# keyboard_board_schematic.net
KiCad netlist of a schematic drawn in EasyEDA Pro
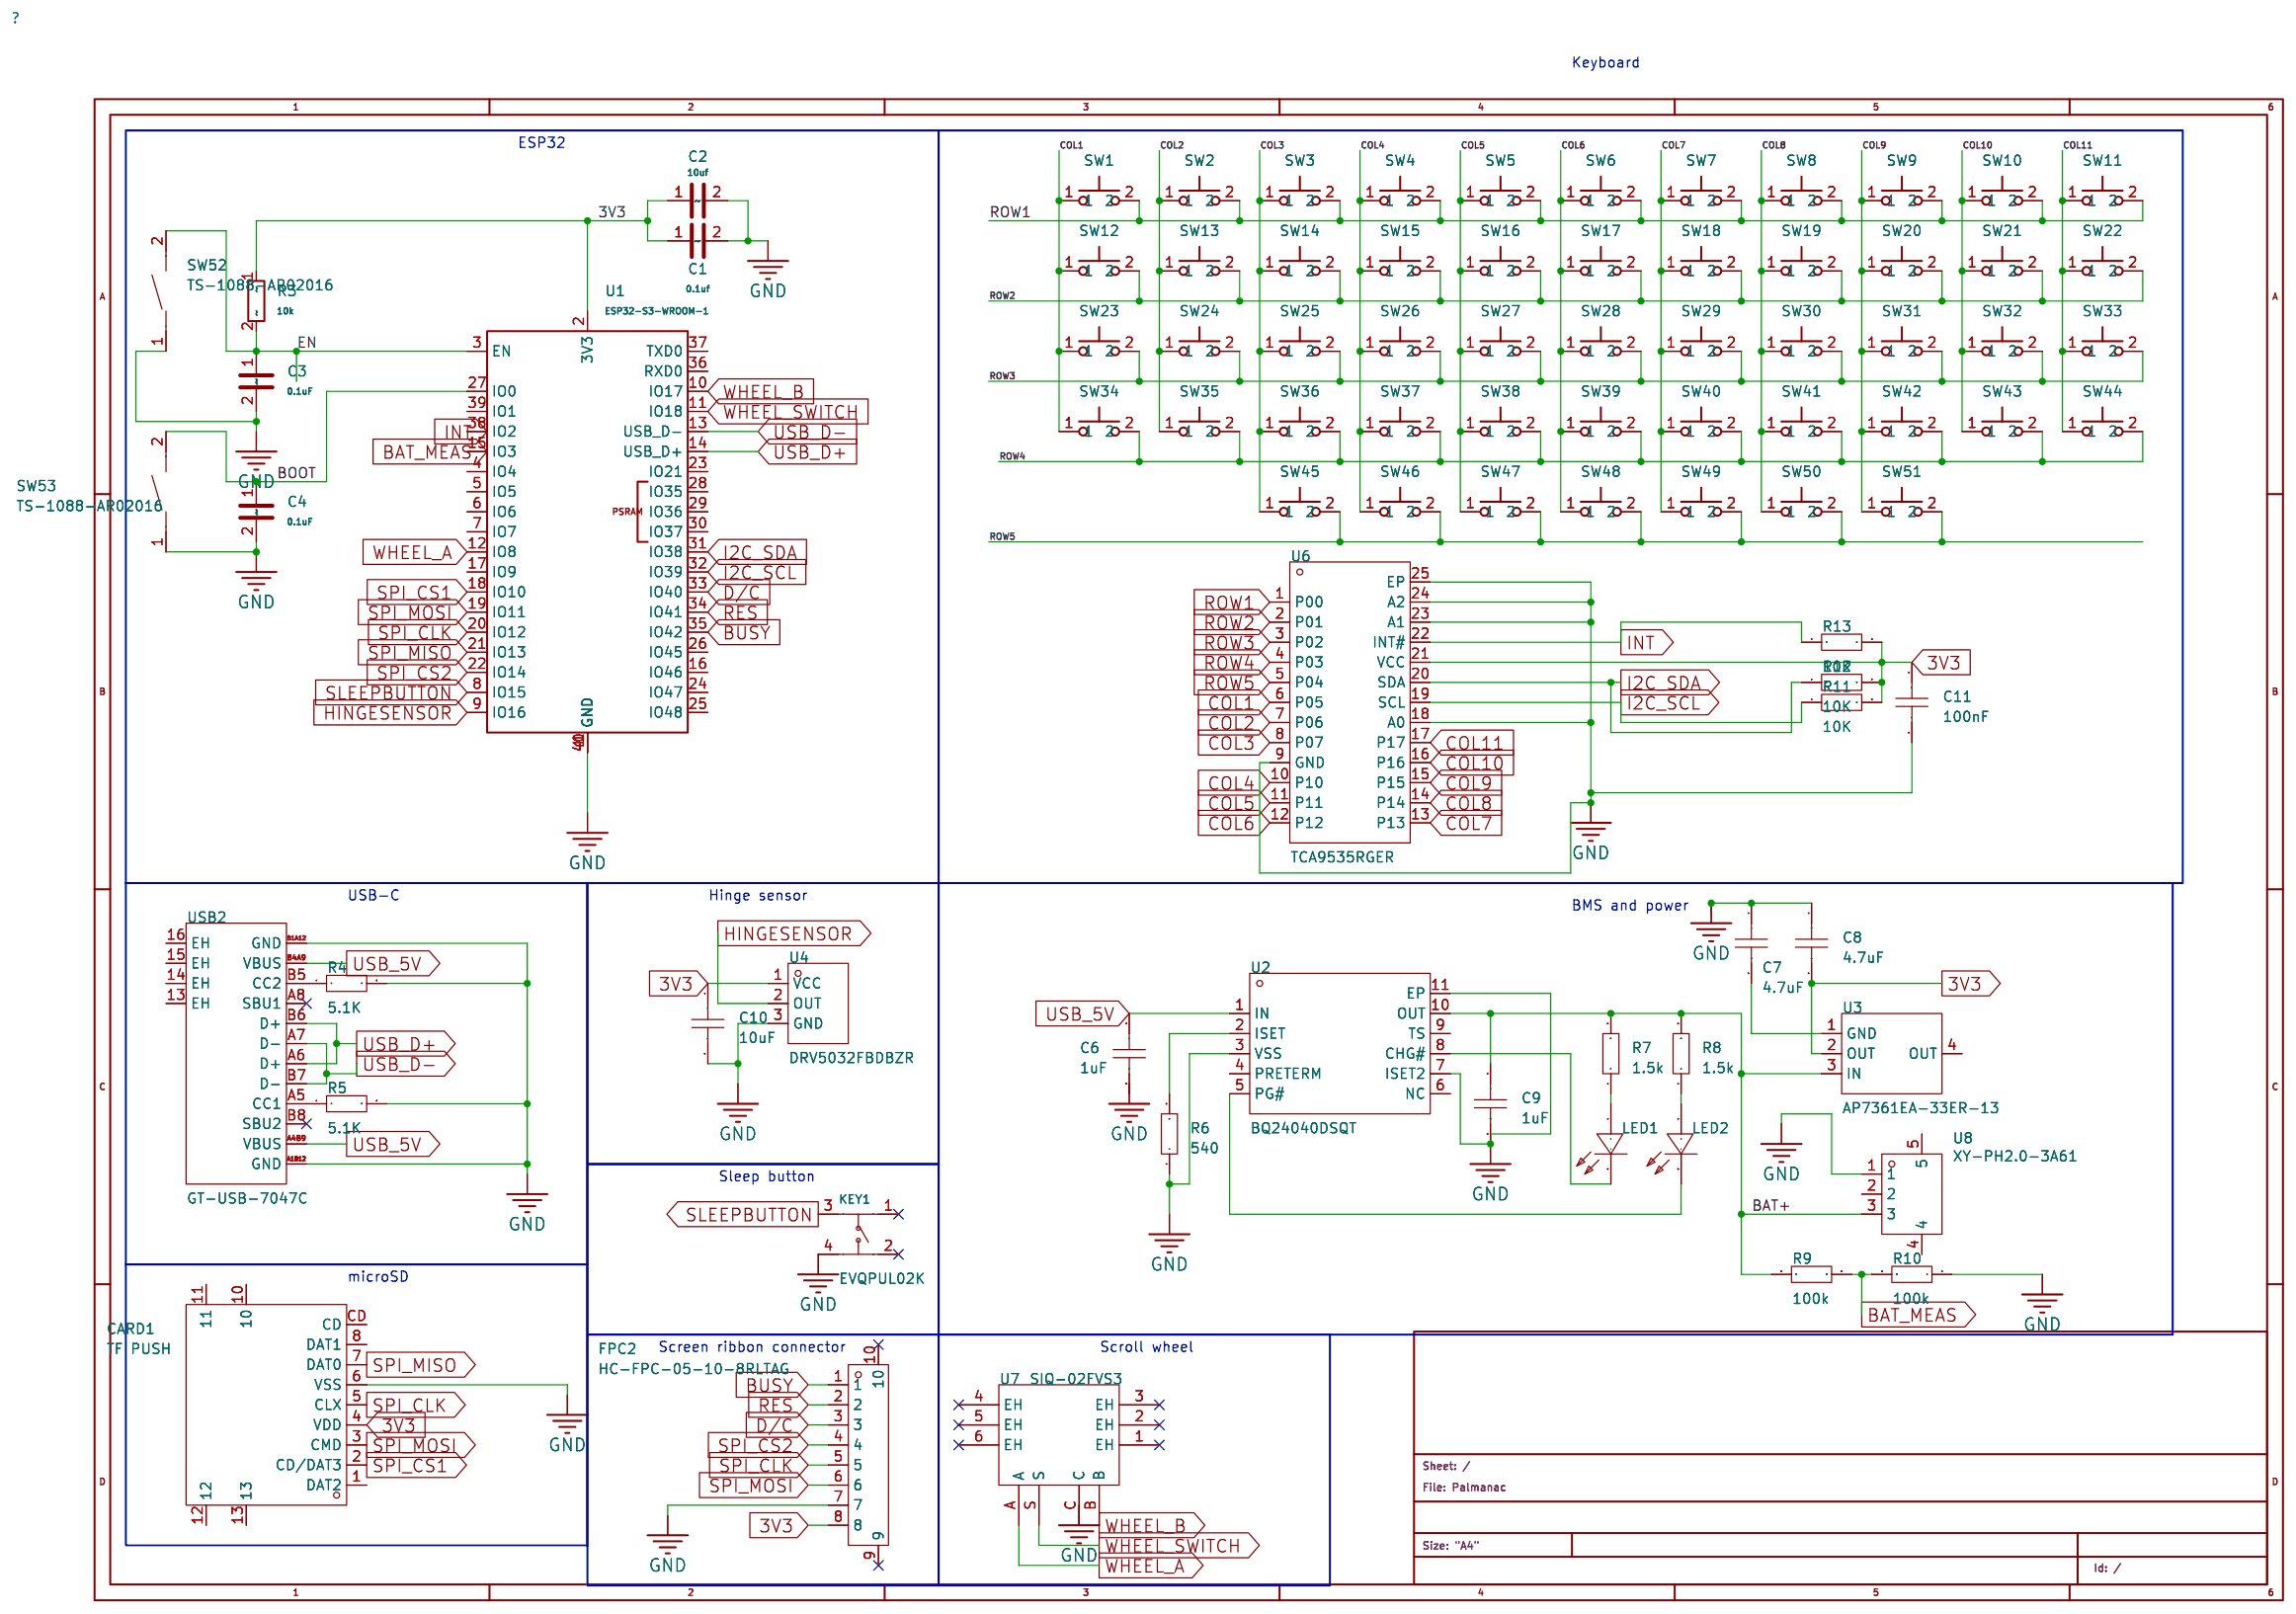
[diagram p0: schematic sheet]

(export (version "E")
  (design (tool "Eeschema 10.0.6"))
  (components
    (comp (ref "C1")
      (value "0.1uf")
      (description "Unpolarized capacitor")
      (libsource (lib "easyedapro") (part "Device_C"))
    )
    (comp (ref "C2")
      (value "10uf")
      (description "Unpolarized capacitor")
      (libsource (lib "easyedapro") (part "Device_C"))
    )
    (comp (ref "C3")
      (value "0.1uF")
      (description "Unpolarized capacitor")
      (libsource (lib "easyedapro") (part "Device_C"))
    )
    (comp (ref "C4")
      (value "0.1uF")
      (description "Unpolarized capacitor")
      (libsource (lib "easyedapro") (part "Device_C"))
    )
    (comp (ref "C6") (value "1uF") (footprint "easyedapro:C0603") (libsource (lib "easyedapro") (part "CAP")))
    (comp (ref "C7")
      (value "4.7uF")
      (footprint "easyedapro:C0603")
      (libsource (lib "easyedapro") (part "CAP"))
    )
    (comp (ref "C8")
      (value "4.7uF")
      (footprint "easyedapro:C0603")
      (libsource (lib "easyedapro") (part "CAP"))
    )
    (comp (ref "C9") (value "1uF") (footprint "easyedapro:C0603") (libsource (lib "easyedapro") (part "CAP")))
    (comp (ref "C10")
      (value "10uF")
      (footprint "easyedapro:C0603")
      (libsource (lib "easyedapro") (part "CAP"))
    )
    (comp (ref "C11")
      (value "100nF")
      (footprint "easyedapro:C0603")
      (libsource (lib "easyedapro") (part "CAP"))
    )
    (comp (ref "CARD1")
      (value "TF PUSH")
      (footprint "easyedapro:TF-SMD_TF-PUSH")
      (fields (field (name "Manufacturer") "SHOU HAN(首韩)"))
      (libsource (lib "easyedapro") (part "TF PUSH"))
    )
    (comp (ref "FPC2")
      (value "HC-FPC-05-10-8RLTAG")
      (footprint "easyedapro:FPC-SMD_8P-P0.50_HCTL_HC-FPC-05-10-8RLTAG")
      (fields (field (name "Manufacturer") "HCTL(华灿天禄)"))
      (libsource (lib "easyedapro") (part "HC-FPC-05-10-8RLTAG"))
    )
    (comp (ref "KEY1")
      (value "EVQPUL02K")
      (footprint "easyedapro:KEY-SMD_4P-L4.7-W3.5-P1.70-LS6.4-EH")
      (fields (field (name "Manufacturer") "PANASONIC(松下)"))
      (libsource (lib "easyedapro") (part "EVQPUL02K"))
    )
    (comp (ref "LED1")
      (value "NCD0805R1")
      (footprint "easyedapro:LED0805-R-RD")
      (fields (field (name "Manufacturer") "国星光电"))
      (libsource (lib "easyedapro") (part "FC-2012HRK-620D"))
    )
    (comp (ref "LED2")
      (value "NCD0805R1")
      (footprint "easyedapro:LED0805-R-RD")
      (fields (field (name "Manufacturer") "国星光电"))
      (libsource (lib "easyedapro") (part "FC-2012HRK-620D"))
    )
    (comp (ref "R3") (value "10k") (description "Resistor") (libsource (lib "easyedapro") (part "Device_R")))
    (comp (ref "R4")
      (value "5.1K")
      (footprint "easyedapro:R0603")
      (libsource (lib "easyedapro") (part "Res"))
    )
    (comp (ref "R5")
      (value "5.1K")
      (footprint "easyedapro:R0603")
      (libsource (lib "easyedapro") (part "Res"))
    )
    (comp (ref "R6") (value "540") (footprint "easyedapro:R0603") (libsource (lib "easyedapro") (part "Res")))
    (comp (ref "R7")
      (value "1.5k")
      (footprint "easyedapro:R0603")
      (libsource (lib "easyedapro") (part "Res"))
    )
    (comp (ref "R8")
      (value "1.5k")
      (footprint "easyedapro:R0603")
      (libsource (lib "easyedapro") (part "Res"))
    )
    (comp (ref "R9")
      (value "100k")
      (footprint "easyedapro:R0603")
      (libsource (lib "easyedapro") (part "Res"))
    )
    (comp (ref "R10")
      (value "100k")
      (footprint "easyedapro:R0603")
      (libsource (lib "easyedapro") (part "Res"))
    )
    (comp (ref "R11")
      (value "10K")
      (footprint "easyedapro:R0603")
      (libsource (lib "easyedapro") (part "Res"))
    )
    (comp (ref "R12")
      (value "10K")
      (footprint "easyedapro:R0603")
      (libsource (lib "easyedapro") (part "Res"))
    )
    (comp (ref "R13")
      (value "10K")
      (footprint "easyedapro:R0603")
      (libsource (lib "easyedapro") (part "Res"))
    )
    (comp (ref "SW1")
      (value "SW_Push")
      (footprint "easyedapro:Switch_Dome_7MM")
      (description "Push button switch, generic, two pins")
      (libsource (lib "easyedapro") (part "Switch_SW_Push"))
    )
    (comp (ref "SW2")
      (value "SW_Push")
      (footprint "easyedapro:Switch_Dome_7MM")
      (description "Push button switch, generic, two pins")
      (libsource (lib "easyedapro") (part "Switch_SW_Push"))
    )
    (comp (ref "SW3")
      (value "SW_Push")
      (footprint "easyedapro:Switch_Dome_7MM")
      (description "Push button switch, generic, two pins")
      (libsource (lib "easyedapro") (part "Switch_SW_Push"))
    )
    (comp (ref "SW4")
      (value "SW_Push")
      (footprint "easyedapro:Switch_Dome_7MM")
      (description "Push button switch, generic, two pins")
      (libsource (lib "easyedapro") (part "Switch_SW_Push"))
    )
    (comp (ref "SW5")
      (value "SW_Push")
      (footprint "easyedapro:Switch_Dome_7MM")
      (description "Push button switch, generic, two pins")
      (libsource (lib "easyedapro") (part "Switch_SW_Push"))
    )
    (comp (ref "SW6")
      (value "SW_Push")
      (footprint "easyedapro:Switch_Dome_7MM")
      (description "Push button switch, generic, two pins")
      (libsource (lib "easyedapro") (part "Switch_SW_Push"))
    )
    (comp (ref "SW7")
      (value "SW_Push")
      (footprint "easyedapro:Switch_Dome_7MM")
      (description "Push button switch, generic, two pins")
      (libsource (lib "easyedapro") (part "Switch_SW_Push"))
    )
    (comp (ref "SW8")
      (value "SW_Push")
      (footprint "easyedapro:Switch_Dome_7MM")
      (description "Push button switch, generic, two pins")
      (libsource (lib "easyedapro") (part "Switch_SW_Push"))
    )
    (comp (ref "SW9")
      (value "SW_Push")
      (footprint "easyedapro:Switch_Dome_7MM")
      (description "Push button switch, generic, two pins")
      (libsource (lib "easyedapro") (part "Switch_SW_Push"))
    )
    (comp (ref "SW10")
      (value "SW_Push")
      (footprint "easyedapro:Switch_Dome_7MM")
      (description "Push button switch, generic, two pins")
      (libsource (lib "easyedapro") (part "Switch_SW_Push"))
    )
    (comp (ref "SW11")
      (value "SW_Push")
      (footprint "easyedapro:Switch_Dome_7MM")
      (description "Push button switch, generic, two pins")
      (libsource (lib "easyedapro") (part "Switch_SW_Push"))
    )
    (comp (ref "SW12")
      (value "SW_Push")
      (footprint "easyedapro:Switch_Dome_7MM")
      (description "Push button switch, generic, two pins")
      (libsource (lib "easyedapro") (part "Switch_SW_Push"))
    )
    (comp (ref "SW13")
      (value "SW_Push")
      (footprint "easyedapro:Switch_Dome_7MM")
      (description "Push button switch, generic, two pins")
      (libsource (lib "easyedapro") (part "Switch_SW_Push"))
    )
    (comp (ref "SW14")
      (value "SW_Push")
      (footprint "easyedapro:Switch_Dome_7MM")
      (description "Push button switch, generic, two pins")
      (libsource (lib "easyedapro") (part "Switch_SW_Push"))
    )
    (comp (ref "SW15")
      (value "SW_Push")
      (footprint "easyedapro:Switch_Dome_7MM")
      (description "Push button switch, generic, two pins")
      (libsource (lib "easyedapro") (part "Switch_SW_Push"))
    )
    (comp (ref "SW16")
      (value "SW_Push")
      (footprint "easyedapro:Switch_Dome_7MM")
      (description "Push button switch, generic, two pins")
      (libsource (lib "easyedapro") (part "Switch_SW_Push"))
    )
    (comp (ref "SW17")
      (value "SW_Push")
      (footprint "easyedapro:Switch_Dome_7MM")
      (description "Push button switch, generic, two pins")
      (libsource (lib "easyedapro") (part "Switch_SW_Push"))
    )
    (comp (ref "SW18")
      (value "SW_Push")
      (footprint "easyedapro:Switch_Dome_7MM")
      (description "Push button switch, generic, two pins")
      (libsource (lib "easyedapro") (part "Switch_SW_Push"))
    )
    (comp (ref "SW19")
      (value "SW_Push")
      (footprint "easyedapro:Switch_Dome_7MM")
      (description "Push button switch, generic, two pins")
      (libsource (lib "easyedapro") (part "Switch_SW_Push"))
    )
    (comp (ref "SW20")
      (value "SW_Push")
      (footprint "easyedapro:Switch_Dome_7MM")
      (description "Push button switch, generic, two pins")
      (libsource (lib "easyedapro") (part "Switch_SW_Push"))
    )
    (comp (ref "SW21")
      (value "SW_Push")
      (footprint "easyedapro:Switch_Dome_7MM")
      (description "Push button switch, generic, two pins")
      (libsource (lib "easyedapro") (part "Switch_SW_Push"))
    )
    (comp (ref "SW22")
      (value "SW_Push")
      (footprint "easyedapro:Switch_Dome_7MM")
      (description "Push button switch, generic, two pins")
      (libsource (lib "easyedapro") (part "Switch_SW_Push"))
    )
    (comp (ref "SW23")
      (value "SW_Push")
      (footprint "easyedapro:Switch_Dome_7MM")
      (description "Push button switch, generic, two pins")
      (libsource (lib "easyedapro") (part "Switch_SW_Push"))
    )
    (comp (ref "SW24")
      (value "SW_Push")
      (footprint "easyedapro:Switch_Dome_7MM")
      (description "Push button switch, generic, two pins")
      (libsource (lib "easyedapro") (part "Switch_SW_Push"))
    )
    (comp (ref "SW25")
      (value "SW_Push")
      (footprint "easyedapro:Switch_Dome_7MM")
      (description "Push button switch, generic, two pins")
      (libsource (lib "easyedapro") (part "Switch_SW_Push"))
    )
    (comp (ref "SW26")
      (value "SW_Push")
      (footprint "easyedapro:Switch_Dome_7MM")
      (description "Push button switch, generic, two pins")
      (libsource (lib "easyedapro") (part "Switch_SW_Push"))
    )
    (comp (ref "SW27")
      (value "SW_Push")
      (footprint "easyedapro:Switch_Dome_7MM")
      (description "Push button switch, generic, two pins")
      (libsource (lib "easyedapro") (part "Switch_SW_Push"))
    )
    (comp (ref "SW28")
      (value "SW_Push")
      (footprint "easyedapro:Switch_Dome_7MM")
      (description "Push button switch, generic, two pins")
      (libsource (lib "easyedapro") (part "Switch_SW_Push"))
    )
    (comp (ref "SW29")
      (value "SW_Push")
      (footprint "easyedapro:Switch_Dome_7MM")
      (description "Push button switch, generic, two pins")
      (libsource (lib "easyedapro") (part "Switch_SW_Push"))
    )
    (comp (ref "SW30")
      (value "SW_Push")
      (footprint "easyedapro:Switch_Dome_7MM")
      (description "Push button switch, generic, two pins")
      (libsource (lib "easyedapro") (part "Switch_SW_Push"))
    )
    (comp (ref "SW31")
      (value "SW_Push")
      (footprint "easyedapro:Switch_Dome_7MM")
      (description "Push button switch, generic, two pins")
      (libsource (lib "easyedapro") (part "Switch_SW_Push"))
    )
    (comp (ref "SW32")
      (value "SW_Push")
      (footprint "easyedapro:Switch_Dome_7MM")
      (description "Push button switch, generic, two pins")
      (libsource (lib "easyedapro") (part "Switch_SW_Push"))
    )
    (comp (ref "SW33")
      (value "SW_Push")
      (footprint "easyedapro:Switch_Dome_7MM")
      (description "Push button switch, generic, two pins")
      (libsource (lib "easyedapro") (part "Switch_SW_Push"))
    )
    (comp (ref "SW34")
      (value "SW_Push")
      (footprint "easyedapro:Switch_Dome_7MM")
      (description "Push button switch, generic, two pins")
      (libsource (lib "easyedapro") (part "Switch_SW_Push"))
    )
    (comp (ref "SW35")
      (value "SW_Push")
      (footprint "easyedapro:Switch_Dome_7MM")
      (description "Push button switch, generic, two pins")
      (libsource (lib "easyedapro") (part "Switch_SW_Push"))
    )
    (comp (ref "SW36")
      (value "SW_Push")
      (footprint "easyedapro:Switch_Dome_7MM")
      (description "Push button switch, generic, two pins")
      (libsource (lib "easyedapro") (part "Switch_SW_Push"))
    )
    (comp (ref "SW37")
      (value "SW_Push")
      (footprint "easyedapro:Switch_Dome_7MM")
      (description "Push button switch, generic, two pins")
      (libsource (lib "easyedapro") (part "Switch_SW_Push"))
    )
    (comp (ref "SW38")
      (value "SW_Push")
      (footprint "easyedapro:Switch_Dome_7MM")
      (description "Push button switch, generic, two pins")
      (libsource (lib "easyedapro") (part "Switch_SW_Push"))
    )
    (comp (ref "SW39")
      (value "SW_Push")
      (footprint "easyedapro:Switch_Dome_7MM")
      (description "Push button switch, generic, two pins")
      (libsource (lib "easyedapro") (part "Switch_SW_Push"))
    )
    (comp (ref "SW40")
      (value "SW_Push")
      (footprint "easyedapro:Switch_Dome_7MM")
      (description "Push button switch, generic, two pins")
      (libsource (lib "easyedapro") (part "Switch_SW_Push"))
    )
    (comp (ref "SW41")
      (value "SW_Push")
      (footprint "easyedapro:Switch_Dome_7MM")
      (description "Push button switch, generic, two pins")
      (libsource (lib "easyedapro") (part "Switch_SW_Push"))
    )
    (comp (ref "SW42")
      (value "SW_Push")
      (footprint "easyedapro:Switch_Dome_7MM")
      (description "Push button switch, generic, two pins")
      (libsource (lib "easyedapro") (part "Switch_SW_Push"))
    )
    (comp (ref "SW43")
      (value "SW_Push")
      (footprint "easyedapro:Switch_Dome_7MM")
      (description "Push button switch, generic, two pins")
      (libsource (lib "easyedapro") (part "Switch_SW_Push"))
    )
    (comp (ref "SW44")
      (value "SW_Push")
      (footprint "easyedapro:Switch_Dome_7MM")
      (description "Push button switch, generic, two pins")
      (libsource (lib "easyedapro") (part "Switch_SW_Push"))
    )
    (comp (ref "SW45")
      (value "SW_Push")
      (footprint "easyedapro:Switch_Dome_7MM")
      (description "Push button switch, generic, two pins")
      (libsource (lib "easyedapro") (part "Switch_SW_Push"))
    )
    (comp (ref "SW46")
      (value "SW_Push")
      (footprint "easyedapro:Switch_Dome_7MM")
      (description "Push button switch, generic, two pins")
      (libsource (lib "easyedapro") (part "Switch_SW_Push"))
    )
    (comp (ref "SW47")
      (value "SW_Push")
      (footprint "easyedapro:Switch_Dome_7MM")
      (description "Push button switch, generic, two pins")
      (libsource (lib "easyedapro") (part "Switch_SW_Push"))
    )
    (comp (ref "SW48")
      (value "SW_Push")
      (footprint "easyedapro:Switch_Dome_7MM")
      (description "Push button switch, generic, two pins")
      (libsource (lib "easyedapro") (part "Switch_SW_Push"))
    )
    (comp (ref "SW49")
      (value "SW_Push")
      (footprint "easyedapro:Switch_Dome_7MM")
      (description "Push button switch, generic, two pins")
      (libsource (lib "easyedapro") (part "Switch_SW_Push"))
    )
    (comp (ref "SW50")
      (value "SW_Push")
      (footprint "easyedapro:Switch_Dome_7MM")
      (description "Push button switch, generic, two pins")
      (libsource (lib "easyedapro") (part "Switch_SW_Push"))
    )
    (comp (ref "SW51")
      (value "SW_Push")
      (footprint "easyedapro:Switch_Dome_7MM")
      (description "Push button switch, generic, two pins")
      (libsource (lib "easyedapro") (part "Switch_SW_Push"))
    )
    (comp (ref "SW52")
      (value "TS-1088-AR02016")
      (footprint "easyedapro:SW-SMD_L3.9-W3.0-P4.45")
      (fields (field (name "Manufacturer") "XUNPU(讯普)"))
      (libsource (lib "easyedapro") (part "TS-1088-AR02016"))
    )
    (comp (ref "SW53")
      (value "TS-1088-AR02016")
      (footprint "easyedapro:SW-SMD_L3.9-W3.0-P4.45")
      (fields (field (name "Manufacturer") "XUNPU(讯普)"))
      (libsource (lib "easyedapro") (part "TS-1088-AR02016"))
    )
    (comp (ref "U1")
      (value "ESP32-S3-WROOM-1")
      (description "RF Module, ESP32-S3 SoC, Wi-Fi 802.11b/g/n, Bluetooth, BLE, 32-bit, 3.3V, onboard antenna, SMD")
      (libsource (lib "easyedapro") (part "RF_Module_ESP32-S3-WROOM-1"))
    )
    (comp (ref "U2")
      (value "BQ24040DSQT")
      (footprint "easyedapro:WSON-10_L2.0-W2.0-P0.40-TL-EP")
      (fields (field (name "Manufacturer") "TI(德州仪器)"))
      (libsource (lib "easyedapro") (part "BQ24040DSQT"))
    )
    (comp (ref "U3")
      (value "AP7361EA-33ER-13")
      (footprint "easyedapro:SOT-223-4_L6.5-W3.5-P2.30-LS7.0-BR")
      (fields (field (name "Manufacturer") "DIODES(美台)"))
      (libsource (lib "easyedapro") (part "AP7361EA-33ER-13"))
    )
    (comp (ref "U4")
      (value "DRV5032FBDBZR")
      (footprint "easyedapro:SOT-23_L2.9-W1.3-P1.90-LS2.4-BR")
      (fields (field (name "Manufacturer") "TI(德州仪器)"))
      (libsource (lib "easyedapro") (part "DRV5032FBDBZR"))
    )
    (comp (ref "U6")
      (value "TCA9535RGER")
      (footprint "easyedapro:VQFN-24_L4.0-W4.0-P0.50-BL-EP2.5")
      (fields (field (name "Manufacturer") "TI(德州仪器)"))
      (libsource (lib "easyedapro") (part "TCA9535RGER"))
    )
    (comp (ref "U7")
      (value "SIQ-02FVS3")
      (footprint "easyedapro:SW-SMD_SIQ-02FVS3_1")
      (fields (field (name "Manufacturer") "MITSUMI(美上美)"))
      (libsource (lib "easyedapro") (part "SIQ-02FVS3"))
    )
    (comp (ref "U8")
      (value "XY-PH2.0-3A61")
      (footprint "easyedapro:CONN-SMD_3P-P2.00_HX-2.0-3P-WT")
      (fields (field (name "Manufacturer") "XYECONN(辛译)"))
      (libsource (lib "easyedapro") (part "XY-PH2.0-3A61"))
    )
    (comp (ref "USB2")
      (value "GT-USB-7047C")
      (footprint "easyedapro:USB-C-SMD_GT-USB-7047C")
      (fields (field (name "Manufacturer") "G-Switch(品赞)"))
      (libsource (lib "easyedapro") (part "GT-USB-7047C"))
    )
  )
  (nets
    (net (code "1") (name "/BAT+") (class "Default")
      (node (ref "C9") (pin "1") (pinfunction "1_1") (pintype "input"))
      (node (ref "R7") (pin "2") (pinfunction "2_2") (pintype "input"))
      (node (ref "R8") (pin "2") (pinfunction "2_2") (pintype "input"))
      (node (ref "R9") (pin "2") (pinfunction "2_2") (pintype "input"))
      (node (ref "U2") (pin "10") (pinfunction "OUT_10") (pintype "unspecified"))
      (node (ref "U3") (pin "3") (pinfunction "IN_3") (pintype "unspecified"))
      (node (ref "U8") (pin "3") (pinfunction "3_3") (pintype "unspecified"))
    )
    (net (code "2") (name "/BOOT") (class "Default")
      (node (ref "C4") (pin "1") (pinfunction "~_1") (pintype "unspecified"))
      (node (ref "SW53") (pin "2") (pinfunction "2_2") (pintype "unspecified"))
      (node (ref "U1") (pin "27") (pinfunction "IO0_27") (pintype "bidirectional"))
    )
    (net (code "3") (name "/EN") (class "Default")
      (node (ref "C3") (pin "1") (pinfunction "~_1") (pintype "unspecified"))
      (node (ref "R3") (pin "2") (pinfunction "~_2") (pintype "unspecified"))
      (node (ref "SW52") (pin "2") (pinfunction "2_2") (pintype "unspecified"))
      (node (ref "U1") (pin "3") (pinfunction "EN_3") (pintype "input"))
    )
    (net (code "4") (name "3V3") (class "Default")
      (node (ref "C1") (pin "1") (pinfunction "~_1") (pintype "unspecified"))
      (node (ref "C10") (pin "1") (pinfunction "1_1") (pintype "input"))
      (node (ref "C11") (pin "1") (pinfunction "1_1") (pintype "input"))
      (node (ref "C2") (pin "1") (pinfunction "~_1") (pintype "unspecified"))
      (node (ref "C8") (pin "2") (pinfunction "2_2") (pintype "input"))
      (node (ref "CARD1") (pin "4") (pinfunction "VDD_4") (pintype "unspecified"))
      (node (ref "FPC2") (pin "8") (pinfunction "8_8") (pintype "unspecified"))
      (node (ref "R11") (pin "2") (pinfunction "2_2") (pintype "input"))
      (node (ref "R12") (pin "2") (pinfunction "2_2") (pintype "input"))
      (node (ref "R13") (pin "2") (pinfunction "2_2") (pintype "input"))
      (node (ref "R3") (pin "1") (pinfunction "~_1") (pintype "unspecified"))
      (node (ref "U1") (pin "2") (pinfunction "3V3_2") (pintype "unspecified"))
      (node (ref "U3") (pin "2") (pinfunction "OUT_2") (pintype "unspecified"))
      (node (ref "U4") (pin "1") (pinfunction "VCC_1") (pintype "unspecified"))
      (node (ref "U6") (pin "21") (pinfunction "VCC_21") (pintype "unspecified"))
    )
    (net (code "5") (name "BAT_MEAS") (class "Default")
      (node (ref "R10") (pin "2") (pinfunction "2_2") (pintype "input"))
      (node (ref "R9") (pin "1") (pinfunction "1_1") (pintype "input"))
      (node (ref "U1") (pin "15") (pinfunction "IO3_15") (pintype "bidirectional"))
    )
    (net (code "6") (name "BUSY") (class "Default")
      (node (ref "FPC2") (pin "1") (pinfunction "1_1") (pintype "unspecified"))
      (node (ref "U1") (pin "35") (pinfunction "IO42_35") (pintype "bidirectional"))
    )
    (net (code "7") (name "COL1") (class "Default")
      (node (ref "SW1") (pin "1") (pinfunction "1_1") (pintype "unspecified"))
      (node (ref "SW12") (pin "1") (pinfunction "1_1") (pintype "unspecified"))
      (node (ref "SW23") (pin "1") (pinfunction "1_1") (pintype "unspecified"))
      (node (ref "SW34") (pin "1") (pinfunction "1_1") (pintype "unspecified"))
      (node (ref "U6") (pin "6") (pinfunction "P05_6") (pintype "unspecified"))
    )
    (net (code "8") (name "COL2") (class "Default")
      (node (ref "SW13") (pin "1") (pinfunction "1_1") (pintype "unspecified"))
      (node (ref "SW2") (pin "1") (pinfunction "1_1") (pintype "unspecified"))
      (node (ref "SW24") (pin "1") (pinfunction "1_1") (pintype "unspecified"))
      (node (ref "SW35") (pin "1") (pinfunction "1_1") (pintype "unspecified"))
      (node (ref "U6") (pin "7") (pinfunction "P06_7") (pintype "unspecified"))
    )
    (net (code "9") (name "COL3") (class "Default")
      (node (ref "SW14") (pin "1") (pinfunction "1_1") (pintype "unspecified"))
      (node (ref "SW25") (pin "1") (pinfunction "1_1") (pintype "unspecified"))
      (node (ref "SW3") (pin "1") (pinfunction "1_1") (pintype "unspecified"))
      (node (ref "SW36") (pin "1") (pinfunction "1_1") (pintype "unspecified"))
      (node (ref "SW45") (pin "1") (pinfunction "1_1") (pintype "unspecified"))
      (node (ref "U6") (pin "8") (pinfunction "P07_8") (pintype "unspecified"))
    )
    (net (code "10") (name "COL4") (class "Default")
      (node (ref "SW15") (pin "1") (pinfunction "1_1") (pintype "unspecified"))
      (node (ref "SW26") (pin "1") (pinfunction "1_1") (pintype "unspecified"))
      (node (ref "SW37") (pin "1") (pinfunction "1_1") (pintype "unspecified"))
      (node (ref "SW4") (pin "1") (pinfunction "1_1") (pintype "unspecified"))
      (node (ref "SW46") (pin "1") (pinfunction "1_1") (pintype "unspecified"))
      (node (ref "U6") (pin "10") (pinfunction "P10_10") (pintype "unspecified"))
    )
    (net (code "11") (name "COL5") (class "Default")
      (node (ref "SW16") (pin "1") (pinfunction "1_1") (pintype "unspecified"))
      (node (ref "SW27") (pin "1") (pinfunction "1_1") (pintype "unspecified"))
      (node (ref "SW38") (pin "1") (pinfunction "1_1") (pintype "unspecified"))
      (node (ref "SW47") (pin "1") (pinfunction "1_1") (pintype "unspecified"))
      (node (ref "SW5") (pin "1") (pinfunction "1_1") (pintype "unspecified"))
      (node (ref "U6") (pin "11") (pinfunction "P11_11") (pintype "unspecified"))
    )
    (net (code "12") (name "COL6") (class "Default")
      (node (ref "SW17") (pin "1") (pinfunction "1_1") (pintype "unspecified"))
      (node (ref "SW28") (pin "1") (pinfunction "1_1") (pintype "unspecified"))
      (node (ref "SW39") (pin "1") (pinfunction "1_1") (pintype "unspecified"))
      (node (ref "SW48") (pin "1") (pinfunction "1_1") (pintype "unspecified"))
      (node (ref "SW6") (pin "1") (pinfunction "1_1") (pintype "unspecified"))
      (node (ref "U6") (pin "12") (pinfunction "P12_12") (pintype "unspecified"))
    )
    (net (code "13") (name "COL7") (class "Default")
      (node (ref "SW18") (pin "1") (pinfunction "1_1") (pintype "unspecified"))
      (node (ref "SW29") (pin "1") (pinfunction "1_1") (pintype "unspecified"))
      (node (ref "SW40") (pin "1") (pinfunction "1_1") (pintype "unspecified"))
      (node (ref "SW49") (pin "1") (pinfunction "1_1") (pintype "unspecified"))
      (node (ref "SW7") (pin "1") (pinfunction "1_1") (pintype "unspecified"))
      (node (ref "U6") (pin "13") (pinfunction "P13_13") (pintype "unspecified"))
    )
    (net (code "14") (name "COL8") (class "Default")
      (node (ref "SW19") (pin "1") (pinfunction "1_1") (pintype "unspecified"))
      (node (ref "SW30") (pin "1") (pinfunction "1_1") (pintype "unspecified"))
      (node (ref "SW41") (pin "1") (pinfunction "1_1") (pintype "unspecified"))
      (node (ref "SW50") (pin "1") (pinfunction "1_1") (pintype "unspecified"))
      (node (ref "SW8") (pin "1") (pinfunction "1_1") (pintype "unspecified"))
      (node (ref "U6") (pin "14") (pinfunction "P14_14") (pintype "unspecified"))
    )
    (net (code "15") (name "COL9") (class "Default")
      (node (ref "SW20") (pin "1") (pinfunction "1_1") (pintype "unspecified"))
      (node (ref "SW31") (pin "1") (pinfunction "1_1") (pintype "unspecified"))
      (node (ref "SW42") (pin "1") (pinfunction "1_1") (pintype "unspecified"))
      (node (ref "SW51") (pin "1") (pinfunction "1_1") (pintype "unspecified"))
      (node (ref "SW9") (pin "1") (pinfunction "1_1") (pintype "unspecified"))
      (node (ref "U6") (pin "15") (pinfunction "P15_15") (pintype "unspecified"))
    )
    (net (code "16") (name "COL10") (class "Default")
      (node (ref "SW10") (pin "1") (pinfunction "1_1") (pintype "unspecified"))
      (node (ref "SW21") (pin "1") (pinfunction "1_1") (pintype "unspecified"))
      (node (ref "SW32") (pin "1") (pinfunction "1_1") (pintype "unspecified"))
      (node (ref "SW43") (pin "1") (pinfunction "1_1") (pintype "unspecified"))
      (node (ref "U6") (pin "16") (pinfunction "P16_16") (pintype "unspecified"))
    )
    (net (code "17") (name "COL11") (class "Default")
      (node (ref "SW11") (pin "1") (pinfunction "1_1") (pintype "unspecified"))
      (node (ref "SW22") (pin "1") (pinfunction "1_1") (pintype "unspecified"))
      (node (ref "SW33") (pin "1") (pinfunction "1_1") (pintype "unspecified"))
      (node (ref "SW44") (pin "1") (pinfunction "1_1") (pintype "unspecified"))
      (node (ref "U6") (pin "17") (pinfunction "P17_17") (pintype "unspecified"))
    )
    (net (code "18") (name "D{slash}C") (class "Default")
      (node (ref "FPC2") (pin "3") (pinfunction "3_3") (pintype "unspecified"))
      (node (ref "U1") (pin "33") (pinfunction "IO40_33") (pintype "bidirectional"))
    )
    (net (code "19") (name "GND") (class "Default")
      (node (ref "C1") (pin "2") (pinfunction "~_2") (pintype "unspecified"))
      (node (ref "C10") (pin "2") (pinfunction "2_2") (pintype "input"))
      (node (ref "C11") (pin "2") (pinfunction "2_2") (pintype "input"))
      (node (ref "C2") (pin "2") (pinfunction "~_2") (pintype "unspecified"))
      (node (ref "C3") (pin "2") (pinfunction "~_2") (pintype "unspecified"))
      (node (ref "C4") (pin "2") (pinfunction "~_2") (pintype "unspecified"))
      (node (ref "C6") (pin "2") (pinfunction "2_2") (pintype "input"))
      (node (ref "C7") (pin "1") (pinfunction "1_1") (pintype "input"))
      (node (ref "C8") (pin "1") (pinfunction "1_1") (pintype "input"))
      (node (ref "C9") (pin "2") (pinfunction "2_2") (pintype "input"))
      (node (ref "CARD1") (pin "6") (pinfunction "VSS_6") (pintype "unspecified"))
      (node (ref "FPC2") (pin "7") (pinfunction "7_7") (pintype "unspecified"))
      (node (ref "KEY1") (pin "4") (pinfunction "4_4") (pintype "input"))
      (node (ref "R10") (pin "1") (pinfunction "1_1") (pintype "input"))
      (node (ref "R4") (pin "2") (pinfunction "2_2") (pintype "input"))
      (node (ref "R5") (pin "2") (pinfunction "2_2") (pintype "input"))
      (node (ref "R6") (pin "1") (pinfunction "1_1") (pintype "input"))
      (node (ref "SW52") (pin "1") (pinfunction "1_1") (pintype "unspecified"))
      (node (ref "SW53") (pin "1") (pinfunction "1_1") (pintype "unspecified"))
      (node (ref "U1") (pin "1") (pinfunction "GND_1") (pintype "unspecified"))
      (node (ref "U1") (pin "40") (pinfunction "GND_40") (pintype "unspecified"))
      (node (ref "U1") (pin "41") (pinfunction "GND_41") (pintype "unspecified"))
      (node (ref "U2") (pin "11") (pinfunction "EP_11") (pintype "unspecified"))
      (node (ref "U2") (pin "3") (pinfunction "VSS_3") (pintype "unspecified"))
      (node (ref "U2") (pin "7") (pinfunction "ISET2_7") (pintype "unspecified"))
      (node (ref "U4") (pin "3") (pinfunction "GND_3") (pintype "unspecified"))
      (node (ref "U6") (pin "18") (pinfunction "A0_18") (pintype "unspecified"))
      (node (ref "U6") (pin "23") (pinfunction "A1_23") (pintype "unspecified"))
      (node (ref "U6") (pin "24") (pinfunction "A2_24") (pintype "unspecified"))
      (node (ref "U6") (pin "25") (pinfunction "EP_25") (pintype "unspecified"))
      (node (ref "U6") (pin "9") (pinfunction "GND_9") (pintype "unspecified"))
      (node (ref "U7") (pin "C") (pinfunction "C_C") (pintype "unspecified"))
      (node (ref "U8") (pin "1") (pinfunction "1_1") (pintype "unspecified"))
      (node (ref "USB2") (pin "A1B12") (pinfunction "GND_A1B12") (pintype "unspecified"))
      (node (ref "USB2") (pin "B1A12") (pinfunction "GND_B1A12") (pintype "unspecified"))
    )
    (net (code "20") (name "HINGESENSOR") (class "Default")
      (node (ref "U1") (pin "9") (pinfunction "IO16_9") (pintype "bidirectional"))
      (node (ref "U4") (pin "2") (pinfunction "OUT_2") (pintype "unspecified"))
    )
    (net (code "21") (name "I2C_SCL") (class "Default")
      (node (ref "R11") (pin "1") (pinfunction "1_1") (pintype "input"))
      (node (ref "U1") (pin "32") (pinfunction "IO39_32") (pintype "bidirectional"))
      (node (ref "U6") (pin "19") (pinfunction "SCL_19") (pintype "unspecified"))
    )
    (net (code "22") (name "I2C_SDA") (class "Default")
      (node (ref "R12") (pin "1") (pinfunction "1_1") (pintype "input"))
      (node (ref "U1") (pin "31") (pinfunction "IO38_31") (pintype "bidirectional"))
      (node (ref "U6") (pin "20") (pinfunction "SDA_20") (pintype "unspecified"))
    )
    (net (code "23") (name "INT") (class "Default")
      (node (ref "R13") (pin "1") (pinfunction "1_1") (pintype "input"))
      (node (ref "U1") (pin "38") (pinfunction "IO2_38") (pintype "bidirectional"))
      (node (ref "U6") (pin "22") (pinfunction "INT#_22") (pintype "unspecified"))
    )
    (net (code "24") (name "Net-(LED1-+)") (class "Default")
      (node (ref "LED1") (pin "1") (pinfunction "+_1") (pintype "unspecified"))
      (node (ref "R7") (pin "1") (pinfunction "1_1") (pintype "input"))
    )
    (net (code "25") (name "Net-(LED1--)") (class "Default")
      (node (ref "LED1") (pin "2") (pinfunction "-_2") (pintype "unspecified"))
      (node (ref "U2") (pin "8") (pinfunction "CHG#_8") (pintype "unspecified"))
    )
    (net (code "26") (name "Net-(LED2-+)") (class "Default")
      (node (ref "LED2") (pin "1") (pinfunction "+_1") (pintype "unspecified"))
      (node (ref "R8") (pin "1") (pinfunction "1_1") (pintype "input"))
    )
    (net (code "27") (name "Net-(LED2--)") (class "Default")
      (node (ref "LED2") (pin "2") (pinfunction "-_2") (pintype "unspecified"))
      (node (ref "U2") (pin "5") (pinfunction "PG#_5") (pintype "unspecified"))
    )
    (net (code "28") (name "Net-(U2-ISET)") (class "Default")
      (node (ref "R6") (pin "2") (pinfunction "2_2") (pintype "input"))
      (node (ref "U2") (pin "2") (pinfunction "ISET_2") (pintype "unspecified"))
    )
    (net (code "29") (name "Net-(U3-GND)") (class "Default")
      (node (ref "C7") (pin "2") (pinfunction "2_2") (pintype "input"))
      (node (ref "U3") (pin "1") (pinfunction "GND_1") (pintype "unspecified"))
    )
    (net (code "30") (name "Net-(USB2-CC1)") (class "Default")
      (node (ref "R5") (pin "1") (pinfunction "1_1") (pintype "input"))
      (node (ref "USB2") (pin "A5") (pinfunction "CC1_A5") (pintype "unspecified"))
    )
    (net (code "31") (name "Net-(USB2-CC2)") (class "Default")
      (node (ref "R4") (pin "1") (pinfunction "1_1") (pintype "input"))
      (node (ref "USB2") (pin "B5") (pinfunction "CC2_B5") (pintype "unspecified"))
    )
    (net (code "32") (name "RES") (class "Default")
      (node (ref "FPC2") (pin "2") (pinfunction "2_2") (pintype "unspecified"))
      (node (ref "U1") (pin "34") (pinfunction "IO41_34") (pintype "bidirectional"))
    )
    (net (code "33") (name "ROW1") (class "Default")
      (node (ref "SW1") (pin "2") (pinfunction "2_2") (pintype "unspecified"))
      (node (ref "SW10") (pin "2") (pinfunction "2_2") (pintype "unspecified"))
      (node (ref "SW11") (pin "2") (pinfunction "2_2") (pintype "unspecified"))
      (node (ref "SW2") (pin "2") (pinfunction "2_2") (pintype "unspecified"))
      (node (ref "SW3") (pin "2") (pinfunction "2_2") (pintype "unspecified"))
      (node (ref "SW4") (pin "2") (pinfunction "2_2") (pintype "unspecified"))
      (node (ref "SW5") (pin "2") (pinfunction "2_2") (pintype "unspecified"))
      (node (ref "SW6") (pin "2") (pinfunction "2_2") (pintype "unspecified"))
      (node (ref "SW7") (pin "2") (pinfunction "2_2") (pintype "unspecified"))
      (node (ref "SW8") (pin "2") (pinfunction "2_2") (pintype "unspecified"))
      (node (ref "SW9") (pin "2") (pinfunction "2_2") (pintype "unspecified"))
      (node (ref "U6") (pin "1") (pinfunction "P00_1") (pintype "unspecified"))
    )
    (net (code "34") (name "ROW2") (class "Default")
      (node (ref "SW12") (pin "2") (pinfunction "2_2") (pintype "unspecified"))
      (node (ref "SW13") (pin "2") (pinfunction "2_2") (pintype "unspecified"))
      (node (ref "SW14") (pin "2") (pinfunction "2_2") (pintype "unspecified"))
      (node (ref "SW15") (pin "2") (pinfunction "2_2") (pintype "unspecified"))
      (node (ref "SW16") (pin "2") (pinfunction "2_2") (pintype "unspecified"))
      (node (ref "SW17") (pin "2") (pinfunction "2_2") (pintype "unspecified"))
      (node (ref "SW18") (pin "2") (pinfunction "2_2") (pintype "unspecified"))
      (node (ref "SW19") (pin "2") (pinfunction "2_2") (pintype "unspecified"))
      (node (ref "SW20") (pin "2") (pinfunction "2_2") (pintype "unspecified"))
      (node (ref "SW21") (pin "2") (pinfunction "2_2") (pintype "unspecified"))
      (node (ref "SW22") (pin "2") (pinfunction "2_2") (pintype "unspecified"))
      (node (ref "U6") (pin "2") (pinfunction "P01_2") (pintype "unspecified"))
    )
    (net (code "35") (name "ROW3") (class "Default")
      (node (ref "SW23") (pin "2") (pinfunction "2_2") (pintype "unspecified"))
      (node (ref "SW24") (pin "2") (pinfunction "2_2") (pintype "unspecified"))
      (node (ref "SW25") (pin "2") (pinfunction "2_2") (pintype "unspecified"))
      (node (ref "SW26") (pin "2") (pinfunction "2_2") (pintype "unspecified"))
      (node (ref "SW27") (pin "2") (pinfunction "2_2") (pintype "unspecified"))
      (node (ref "SW28") (pin "2") (pinfunction "2_2") (pintype "unspecified"))
      (node (ref "SW29") (pin "2") (pinfunction "2_2") (pintype "unspecified"))
      (node (ref "SW30") (pin "2") (pinfunction "2_2") (pintype "unspecified"))
      (node (ref "SW31") (pin "2") (pinfunction "2_2") (pintype "unspecified"))
      (node (ref "SW32") (pin "2") (pinfunction "2_2") (pintype "unspecified"))
      (node (ref "SW33") (pin "2") (pinfunction "2_2") (pintype "unspecified"))
      (node (ref "U6") (pin "3") (pinfunction "P02_3") (pintype "unspecified"))
    )
    (net (code "36") (name "ROW4") (class "Default")
      (node (ref "SW34") (pin "2") (pinfunction "2_2") (pintype "unspecified"))
      (node (ref "SW35") (pin "2") (pinfunction "2_2") (pintype "unspecified"))
      (node (ref "SW36") (pin "2") (pinfunction "2_2") (pintype "unspecified"))
      (node (ref "SW37") (pin "2") (pinfunction "2_2") (pintype "unspecified"))
      (node (ref "SW38") (pin "2") (pinfunction "2_2") (pintype "unspecified"))
      (node (ref "SW39") (pin "2") (pinfunction "2_2") (pintype "unspecified"))
      (node (ref "SW40") (pin "2") (pinfunction "2_2") (pintype "unspecified"))
      (node (ref "SW41") (pin "2") (pinfunction "2_2") (pintype "unspecified"))
      (node (ref "SW42") (pin "2") (pinfunction "2_2") (pintype "unspecified"))
      (node (ref "SW43") (pin "2") (pinfunction "2_2") (pintype "unspecified"))
      (node (ref "SW44") (pin "2") (pinfunction "2_2") (pintype "unspecified"))
      (node (ref "U6") (pin "4") (pinfunction "P03_4") (pintype "unspecified"))
    )
    (net (code "37") (name "ROW5") (class "Default")
      (node (ref "SW45") (pin "2") (pinfunction "2_2") (pintype "unspecified"))
      (node (ref "SW46") (pin "2") (pinfunction "2_2") (pintype "unspecified"))
      (node (ref "SW47") (pin "2") (pinfunction "2_2") (pintype "unspecified"))
      (node (ref "SW48") (pin "2") (pinfunction "2_2") (pintype "unspecified"))
      (node (ref "SW49") (pin "2") (pinfunction "2_2") (pintype "unspecified"))
      (node (ref "SW50") (pin "2") (pinfunction "2_2") (pintype "unspecified"))
      (node (ref "SW51") (pin "2") (pinfunction "2_2") (pintype "unspecified"))
      (node (ref "U6") (pin "5") (pinfunction "P04_5") (pintype "unspecified"))
    )
    (net (code "38") (name "SLEEPBUTTON") (class "Default")
      (node (ref "KEY1") (pin "3") (pinfunction "3_3") (pintype "input"))
      (node (ref "U1") (pin "8") (pinfunction "IO15_8") (pintype "bidirectional"))
    )
    (net (code "39") (name "SPI_CLK") (class "Default")
      (node (ref "CARD1") (pin "5") (pinfunction "CLX_5") (pintype "unspecified"))
      (node (ref "FPC2") (pin "5") (pinfunction "5_5") (pintype "unspecified"))
      (node (ref "U1") (pin "20") (pinfunction "IO12_20") (pintype "bidirectional"))
    )
    (net (code "40") (name "SPI_CS1") (class "Default")
      (node (ref "CARD1") (pin "2") (pinfunction "CD/DAT3_2") (pintype "unspecified"))
      (node (ref "U1") (pin "18") (pinfunction "IO10_18") (pintype "bidirectional"))
    )
    (net (code "41") (name "SPI_CS2") (class "Default")
      (node (ref "FPC2") (pin "4") (pinfunction "4_4") (pintype "unspecified"))
      (node (ref "U1") (pin "22") (pinfunction "IO14_22") (pintype "bidirectional"))
    )
    (net (code "42") (name "SPI_MISO") (class "Default")
      (node (ref "CARD1") (pin "7") (pinfunction "DAT0_7") (pintype "unspecified"))
      (node (ref "U1") (pin "21") (pinfunction "IO13_21") (pintype "bidirectional"))
    )
    (net (code "43") (name "SPI_MOSI") (class "Default")
      (node (ref "CARD1") (pin "3") (pinfunction "CMD_3") (pintype "unspecified"))
      (node (ref "FPC2") (pin "6") (pinfunction "6_6") (pintype "unspecified"))
      (node (ref "U1") (pin "19") (pinfunction "IO11_19") (pintype "bidirectional"))
    )
    (net (code "44") (name "USB_5V") (class "Default")
      (node (ref "C6") (pin "1") (pinfunction "1_1") (pintype "input"))
      (node (ref "U2") (pin "1") (pinfunction "IN_1") (pintype "unspecified"))
      (node (ref "USB2") (pin "A4B9") (pinfunction "VBUS_A4B9") (pintype "unspecified"))
      (node (ref "USB2") (pin "B4A9") (pinfunction "VBUS_B4A9") (pintype "unspecified"))
    )
    (net (code "45") (name "USB_D+") (class "Default")
      (node (ref "U1") (pin "14") (pinfunction "USB_D+_14") (pintype "bidirectional"))
      (node (ref "USB2") (pin "A6") (pinfunction "D+_A6") (pintype "unspecified"))
      (node (ref "USB2") (pin "B6") (pinfunction "D+_B6") (pintype "unspecified"))
    )
    (net (code "46") (name "USB_D-") (class "Default")
      (node (ref "U1") (pin "13") (pinfunction "USB_D-_13") (pintype "bidirectional"))
      (node (ref "USB2") (pin "A7") (pinfunction "D-_A7") (pintype "unspecified"))
      (node (ref "USB2") (pin "B7") (pinfunction "D-_B7") (pintype "unspecified"))
    )
    (net (code "47") (name "WHEEL_A") (class "Default")
      (node (ref "U1") (pin "12") (pinfunction "IO8_12") (pintype "bidirectional"))
      (node (ref "U7") (pin "A") (pinfunction "A_A") (pintype "unspecified"))
    )
    (net (code "48") (name "WHEEL_B") (class "Default")
      (node (ref "U1") (pin "10") (pinfunction "IO17_10") (pintype "bidirectional"))
      (node (ref "U7") (pin "B") (pinfunction "B_B") (pintype "unspecified"))
    )
    (net (code "49") (name "WHEEL_SWITCH") (class "Default")
      (node (ref "U1") (pin "11") (pinfunction "IO18_11") (pintype "bidirectional"))
      (node (ref "U7") (pin "S") (pinfunction "S_S") (pintype "unspecified"))
    )
    (net (code "50") (name "unconnected-(CARD1-DAT1-Pad8)") (class "Default")
      (node (ref "CARD1") (pin "8") (pinfunction "DAT1_8") (pintype "unspecified"))
    )
    (net (code "51") (name "unconnected-(CARD1-DAT2-Pad1)") (class "Default")
      (node (ref "CARD1") (pin "1") (pinfunction "DAT2_1") (pintype "unspecified"))
    )
    (net (code "52") (name "unconnected-(CARD1-Pad10)") (class "Default")
      (node (ref "CARD1") (pin "10") (pinfunction "10_10") (pintype "unspecified"))
    )
    (net (code "53") (name "unconnected-(CARD1-Pad11)") (class "Default")
      (node (ref "CARD1") (pin "11") (pinfunction "11_11") (pintype "unspecified"))
    )
    (net (code "54") (name "unconnected-(CARD1-Pad12)") (class "Default")
      (node (ref "CARD1") (pin "12") (pinfunction "12_12") (pintype "unspecified"))
    )
    (net (code "55") (name "unconnected-(CARD1-Pad13)") (class "Default")
      (node (ref "CARD1") (pin "13") (pinfunction "13_13") (pintype "unspecified"))
    )
    (net (code "56") (name "unconnected-(CARD1-PadCD)") (class "Default")
      (node (ref "CARD1") (pin "CD") (pinfunction "CD_CD") (pintype "unspecified"))
    )
    (net (code "57") (name "unconnected-(FPC2-Pad9)") (class "Default")
      (node (ref "FPC2") (pin "9") (pinfunction "9_9") (pintype "unspecified+no_connect"))
    )
    (net (code "58") (name "unconnected-(FPC2-Pad10)") (class "Default")
      (node (ref "FPC2") (pin "10") (pinfunction "10_10") (pintype "unspecified+no_connect"))
    )
    (net (code "59") (name "unconnected-(KEY1-Pad1)") (class "Default")
      (node (ref "KEY1") (pin "1") (pinfunction "1_1") (pintype "input+no_connect"))
    )
    (net (code "60") (name "unconnected-(KEY1-Pad2)") (class "Default")
      (node (ref "KEY1") (pin "2") (pinfunction "2_2") (pintype "input+no_connect"))
    )
    (net (code "61") (name "unconnected-(U1-IO1-Pad39)") (class "Default")
      (node (ref "U1") (pin "39") (pinfunction "IO1_39") (pintype "bidirectional"))
    )
    (net (code "62") (name "unconnected-(U1-IO4-Pad4)") (class "Default")
      (node (ref "U1") (pin "4") (pinfunction "IO4_4") (pintype "bidirectional"))
    )
    (net (code "63") (name "unconnected-(U1-IO5-Pad5)") (class "Default")
      (node (ref "U1") (pin "5") (pinfunction "IO5_5") (pintype "bidirectional"))
    )
    (net (code "64") (name "unconnected-(U1-IO6-Pad6)") (class "Default")
      (node (ref "U1") (pin "6") (pinfunction "IO6_6") (pintype "bidirectional"))
    )
    (net (code "65") (name "unconnected-(U1-IO7-Pad7)") (class "Default")
      (node (ref "U1") (pin "7") (pinfunction "IO7_7") (pintype "bidirectional"))
    )
    (net (code "66") (name "unconnected-(U1-IO9-Pad17)") (class "Default")
      (node (ref "U1") (pin "17") (pinfunction "IO9_17") (pintype "bidirectional"))
    )
    (net (code "67") (name "unconnected-(U1-IO21-Pad23)") (class "Default")
      (node (ref "U1") (pin "23") (pinfunction "IO21_23") (pintype "bidirectional"))
    )
    (net (code "68") (name "unconnected-(U1-IO35-Pad28)") (class "Default")
      (node (ref "U1") (pin "28") (pinfunction "IO35_28") (pintype "bidirectional"))
    )
    (net (code "69") (name "unconnected-(U1-IO36-Pad29)") (class "Default")
      (node (ref "U1") (pin "29") (pinfunction "IO36_29") (pintype "bidirectional"))
    )
    (net (code "70") (name "unconnected-(U1-IO37-Pad30)") (class "Default")
      (node (ref "U1") (pin "30") (pinfunction "IO37_30") (pintype "bidirectional"))
    )
    (net (code "71") (name "unconnected-(U1-IO45-Pad26)") (class "Default")
      (node (ref "U1") (pin "26") (pinfunction "IO45_26") (pintype "bidirectional"))
    )
    (net (code "72") (name "unconnected-(U1-IO46-Pad16)") (class "Default")
      (node (ref "U1") (pin "16") (pinfunction "IO46_16") (pintype "bidirectional"))
    )
    (net (code "73") (name "unconnected-(U1-IO47-Pad24)") (class "Default")
      (node (ref "U1") (pin "24") (pinfunction "IO47_24") (pintype "bidirectional"))
    )
    (net (code "74") (name "unconnected-(U1-IO48-Pad25)") (class "Default")
      (node (ref "U1") (pin "25") (pinfunction "IO48_25") (pintype "bidirectional"))
    )
    (net (code "75") (name "unconnected-(U1-RXD0-Pad36)") (class "Default")
      (node (ref "U1") (pin "36") (pinfunction "RXD0_36") (pintype "bidirectional"))
    )
    (net (code "76") (name "unconnected-(U1-TXD0-Pad37)") (class "Default")
      (node (ref "U1") (pin "37") (pinfunction "TXD0_37") (pintype "bidirectional"))
    )
    (net (code "77") (name "unconnected-(U2-NC-Pad6)") (class "Default")
      (node (ref "U2") (pin "6") (pinfunction "NC_6") (pintype "unspecified"))
    )
    (net (code "78") (name "unconnected-(U2-PRETERM-Pad4)") (class "Default")
      (node (ref "U2") (pin "4") (pinfunction "PRETERM_4") (pintype "unspecified"))
    )
    (net (code "79") (name "unconnected-(U2-TS-Pad9)") (class "Default")
      (node (ref "U2") (pin "9") (pinfunction "TS_9") (pintype "unspecified"))
    )
    (net (code "80") (name "unconnected-(U3-OUT-Pad4)") (class "Default")
      (node (ref "U3") (pin "4") (pinfunction "OUT_4") (pintype "unspecified"))
    )
    (net (code "81") (name "unconnected-(U7-EH-Pad1)") (class "Default")
      (node (ref "U7") (pin "1") (pinfunction "EH_1") (pintype "unspecified+no_connect"))
    )
    (net (code "82") (name "unconnected-(U7-EH-Pad2)") (class "Default")
      (node (ref "U7") (pin "2") (pinfunction "EH_2") (pintype "unspecified+no_connect"))
    )
    (net (code "83") (name "unconnected-(U7-EH-Pad3)") (class "Default")
      (node (ref "U7") (pin "3") (pinfunction "EH_3") (pintype "unspecified+no_connect"))
    )
    (net (code "84") (name "unconnected-(U7-EH-Pad4)") (class "Default")
      (node (ref "U7") (pin "4") (pinfunction "EH_4") (pintype "unspecified+no_connect"))
    )
    (net (code "85") (name "unconnected-(U7-EH-Pad5)") (class "Default")
      (node (ref "U7") (pin "5") (pinfunction "EH_5") (pintype "unspecified+no_connect"))
    )
    (net (code "86") (name "unconnected-(U7-EH-Pad6)") (class "Default")
      (node (ref "U7") (pin "6") (pinfunction "EH_6") (pintype "unspecified+no_connect"))
    )
    (net (code "87") (name "unconnected-(U8-Pad2)") (class "Default")
      (node (ref "U8") (pin "2") (pinfunction "2_2") (pintype "unspecified"))
    )
    (net (code "88") (name "unconnected-(U8-Pad4)") (class "Default")
      (node (ref "U8") (pin "4") (pinfunction "4_4") (pintype "unspecified"))
    )
    (net (code "89") (name "unconnected-(U8-Pad5)") (class "Default")
      (node (ref "U8") (pin "5") (pinfunction "5_5") (pintype "unspecified"))
    )
    (net (code "90") (name "unconnected-(USB2-EH-Pad13)") (class "Default")
      (node (ref "USB2") (pin "13") (pinfunction "EH_13") (pintype "unspecified"))
    )
    (net (code "91") (name "unconnected-(USB2-EH-Pad14)") (class "Default")
      (node (ref "USB2") (pin "14") (pinfunction "EH_14") (pintype "unspecified"))
    )
    (net (code "92") (name "unconnected-(USB2-EH-Pad15)") (class "Default")
      (node (ref "USB2") (pin "15") (pinfunction "EH_15") (pintype "unspecified"))
    )
    (net (code "93") (name "unconnected-(USB2-EH-Pad16)") (class "Default")
      (node (ref "USB2") (pin "16") (pinfunction "EH_16") (pintype "unspecified"))
    )
    (net (code "94") (name "unconnected-(USB2-SBU1-PadA8)") (class "Default")
      (node (ref "USB2") (pin "A8") (pinfunction "SBU1_A8") (pintype "unspecified+no_connect"))
    )
    (net (code "95") (name "unconnected-(USB2-SBU2-PadB8)") (class "Default")
      (node (ref "USB2") (pin "B8") (pinfunction "SBU2_B8") (pintype "unspecified+no_connect"))
    )
  )
)
